# lis3dsh_i2c.net
KiCad netlist of a schematic drawn in Altium Designer
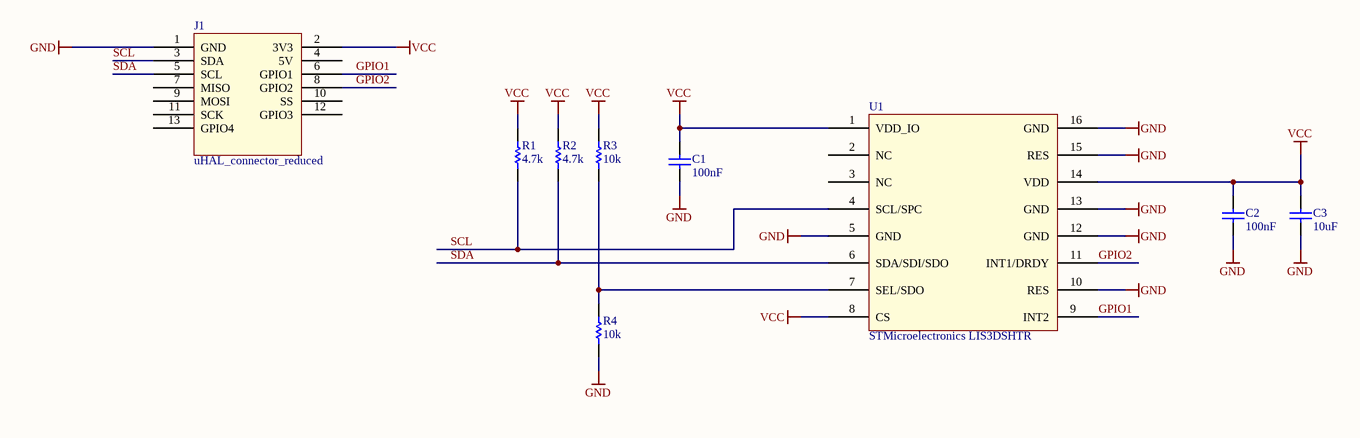
[diagram p0: lis3dsh_i2c.SchDoc]

(export (version "E")
  (design (tool "Eeschema 10.0.6"))
  (components
    (comp (ref "C1")
      (value "Murata GCM188R71H104KA57D")
      (footprint "CAPC1608X90X35ML10T15")
      (description "CAP CER 0.1UF 50V 10% X7R 0603")
      (fields (field (name "CAPACITANCE") "100nF"))
      (libsource (lib "CommunityVault") (part "CMP-119667-3"))
    )
    (comp (ref "C2")
      (value "Murata GCM188R71H104KA57D")
      (footprint "CAPC1608X90X35ML10T15")
      (description "CAP CER 0.1UF 50V 10% X7R 0603")
      (fields (field (name "CAPACITANCE") "100nF"))
      (libsource (lib "CommunityVault") (part "CMP-119667-3"))
    )
    (comp (ref "C3")
      (value "Murata GCM188R71H104KA57D")
      (footprint "CAPC1608X90X35ML10T15")
      (description "CAP CER 0.1UF 50V 10% X7R 0603")
      (fields (field (name "CAPACITANCE") "10uF"))
      (libsource (lib "CommunityVault") (part "CMP-119667-3"))
    )
    (comp (ref "J1")
      (value "uHAL_connector_reduced")
      (footprint "PCB-45ncoppm4oopozvqifsq-1")
      (description "connector for uHAL with reduced pin number")
      (libsource (lib "CommunityVault") (part "CMP-2q23h2cwhjlfm8s6r7i8-1"))
    )
    (comp (ref "R1")
      (value "4.7k")
      (footprint "RESC1608X05N")
      (description "RCA Series 0603 0.1 W 0 O Jumper Surface Mount Thick Film Chip Resistor")
      (fields (field (name "MANUFACTURER PART NUMBER") "RCA06030000ZSEA"))
      (libsource (lib "CommunityVault") (part "SYM-31acf99032f6ee6b-1"))
    )
    (comp (ref "R2")
      (value "4.7k")
      (footprint "RESC1608X05N")
      (description "RCA Series 0603 0.1 W 0 O Jumper Surface Mount Thick Film Chip Resistor")
      (fields (field (name "MANUFACTURER PART NUMBER") "RCA06030000ZSEA"))
      (libsource (lib "CommunityVault") (part "SYM-31acf99032f6ee6b-1"))
    )
    (comp (ref "R3")
      (value "10k")
      (footprint "RESC1608X05N")
      (description "RCA Series 0603 0.1 W 0 O Jumper Surface Mount Thick Film Chip Resistor")
      (fields (field (name "MANUFACTURER PART NUMBER") "RCA06030000ZSEA"))
      (libsource (lib "CommunityVault") (part "SYM-31acf99032f6ee6b-1"))
    )
    (comp (ref "R4")
      (value "10k")
      (footprint "RESC1608X05N")
      (description "RCA Series 0603 0.1 W 0 O Jumper Surface Mount Thick Film Chip Resistor")
      (fields (field (name "MANUFACTURER PART NUMBER") "RCA06030000ZSEA"))
      (libsource (lib "CommunityVault") (part "SYM-31acf99032f6ee6b-1"))
    )
    (comp (ref "U1")
      (value "STMicroelectronics LIS3DSHTR")
      (footprint "STM-LGA-16_M")
      (description "MEMS digital output motion sensor: ultra low-power high performance 3-axes nano accelerometer")
      (libsource (lib "CommunityVault") (part "CMP-40c388997c2c9f04-1"))
    )
  )
  (nets
    (net (code "1") (name "/GPIO1") (class "Default")
      (node (ref "J1") (pin "6") (pinfunction "GPIO1_6") (pintype "passive"))
      (node (ref "U1") (pin "9") (pinfunction "INT2_9") (pintype "passive"))
    )
    (net (code "2") (name "/GPIO2") (class "Default")
      (node (ref "J1") (pin "8") (pinfunction "GPIO2_8") (pintype "passive"))
      (node (ref "U1") (pin "11") (pinfunction "INT1/DRDY_11") (pintype "passive"))
    )
    (net (code "3") (name "/SCL") (class "Default")
      (node (ref "J1") (pin "3") (pinfunction "SDA_3") (pintype "passive"))
      (node (ref "R1") (pin "1") (pinfunction "1_1") (pintype "passive"))
      (node (ref "U1") (pin "4") (pinfunction "SCL/SPC_4") (pintype "passive"))
    )
    (net (code "4") (name "/SDA") (class "Default")
      (node (ref "J1") (pin "5") (pinfunction "SCL_5") (pintype "passive"))
      (node (ref "R2") (pin "1") (pinfunction "1_1") (pintype "passive"))
      (node (ref "U1") (pin "6") (pinfunction "SDA/SDI/SDO_6") (pintype "passive"))
    )
    (net (code "5") (name "GND") (class "Default")
      (node (ref "C1") (pin "2") (pinfunction "2_2") (pintype "passive"))
      (node (ref "C2") (pin "2") (pinfunction "2_2") (pintype "passive"))
      (node (ref "C3") (pin "2") (pinfunction "2_2") (pintype "passive"))
      (node (ref "J1") (pin "1") (pinfunction "GND_1") (pintype "passive"))
      (node (ref "R4") (pin "1") (pinfunction "1_1") (pintype "passive"))
      (node (ref "U1") (pin "10") (pinfunction "RES_10") (pintype "passive"))
      (node (ref "U1") (pin "12") (pinfunction "GND_12") (pintype "passive"))
      (node (ref "U1") (pin "13") (pinfunction "GND_13") (pintype "passive"))
      (node (ref "U1") (pin "15") (pinfunction "RES_15") (pintype "passive"))
      (node (ref "U1") (pin "16") (pinfunction "GND_16") (pintype "passive"))
      (node (ref "U1") (pin "5") (pinfunction "GND_5") (pintype "passive"))
    )
    (net (code "6") (name "Net-(U1-SEL{slash}SDO)") (class "Default")
      (node (ref "R3") (pin "1") (pinfunction "1_1") (pintype "passive"))
      (node (ref "R4") (pin "2") (pinfunction "2_2") (pintype "passive"))
      (node (ref "U1") (pin "7") (pinfunction "SEL/SDO_7") (pintype "passive"))
    )
    (net (code "7") (name "VCC") (class "Default")
      (node (ref "C1") (pin "1") (pinfunction "1_1") (pintype "passive"))
      (node (ref "C2") (pin "1") (pinfunction "1_1") (pintype "passive"))
      (node (ref "C3") (pin "1") (pinfunction "1_1") (pintype "passive"))
      (node (ref "J1") (pin "2") (pinfunction "3V3_2") (pintype "passive"))
      (node (ref "R1") (pin "2") (pinfunction "2_2") (pintype "passive"))
      (node (ref "R2") (pin "2") (pinfunction "2_2") (pintype "passive"))
      (node (ref "R3") (pin "2") (pinfunction "2_2") (pintype "passive"))
      (node (ref "U1") (pin "1") (pinfunction "VDD_IO_1") (pintype "passive"))
      (node (ref "U1") (pin "14") (pinfunction "VDD_14") (pintype "passive"))
      (node (ref "U1") (pin "8") (pinfunction "CS_8") (pintype "passive"))
    )
    (net (code "8") (name "unconnected-(J1-5V-Pad4)") (class "Default")
      (node (ref "J1") (pin "4") (pinfunction "5V_4") (pintype "passive"))
    )
    (net (code "9") (name "unconnected-(J1-GPIO3-Pad12)") (class "Default")
      (node (ref "J1") (pin "12") (pinfunction "GPIO3_12") (pintype "passive"))
    )
    (net (code "10") (name "unconnected-(J1-GPIO4-Pad13)") (class "Default")
      (node (ref "J1") (pin "13") (pinfunction "GPIO4_13") (pintype "passive"))
    )
    (net (code "11") (name "unconnected-(J1-MISO-Pad7)") (class "Default")
      (node (ref "J1") (pin "7") (pinfunction "MISO_7") (pintype "passive"))
    )
    (net (code "12") (name "unconnected-(J1-MOSI-Pad9)") (class "Default")
      (node (ref "J1") (pin "9") (pinfunction "MOSI_9") (pintype "passive"))
    )
    (net (code "13") (name "unconnected-(J1-SCK-Pad11)") (class "Default")
      (node (ref "J1") (pin "11") (pinfunction "SCK_11") (pintype "passive"))
    )
    (net (code "14") (name "unconnected-(J1-SS-Pad10)") (class "Default")
      (node (ref "J1") (pin "10") (pinfunction "SS_10") (pintype "passive"))
    )
    (net (code "15") (name "unconnected-(U1-NC-Pad2)") (class "Default")
      (node (ref "U1") (pin "2") (pinfunction "NC_2") (pintype "passive"))
    )
    (net (code "16") (name "unconnected-(U1-NC-Pad3)") (class "Default")
      (node (ref "U1") (pin "3") (pinfunction "NC_3") (pintype "passive"))
    )
  )
)
